# ESP32.net
KiCad netlist of a schematic drawn in Altium Designer
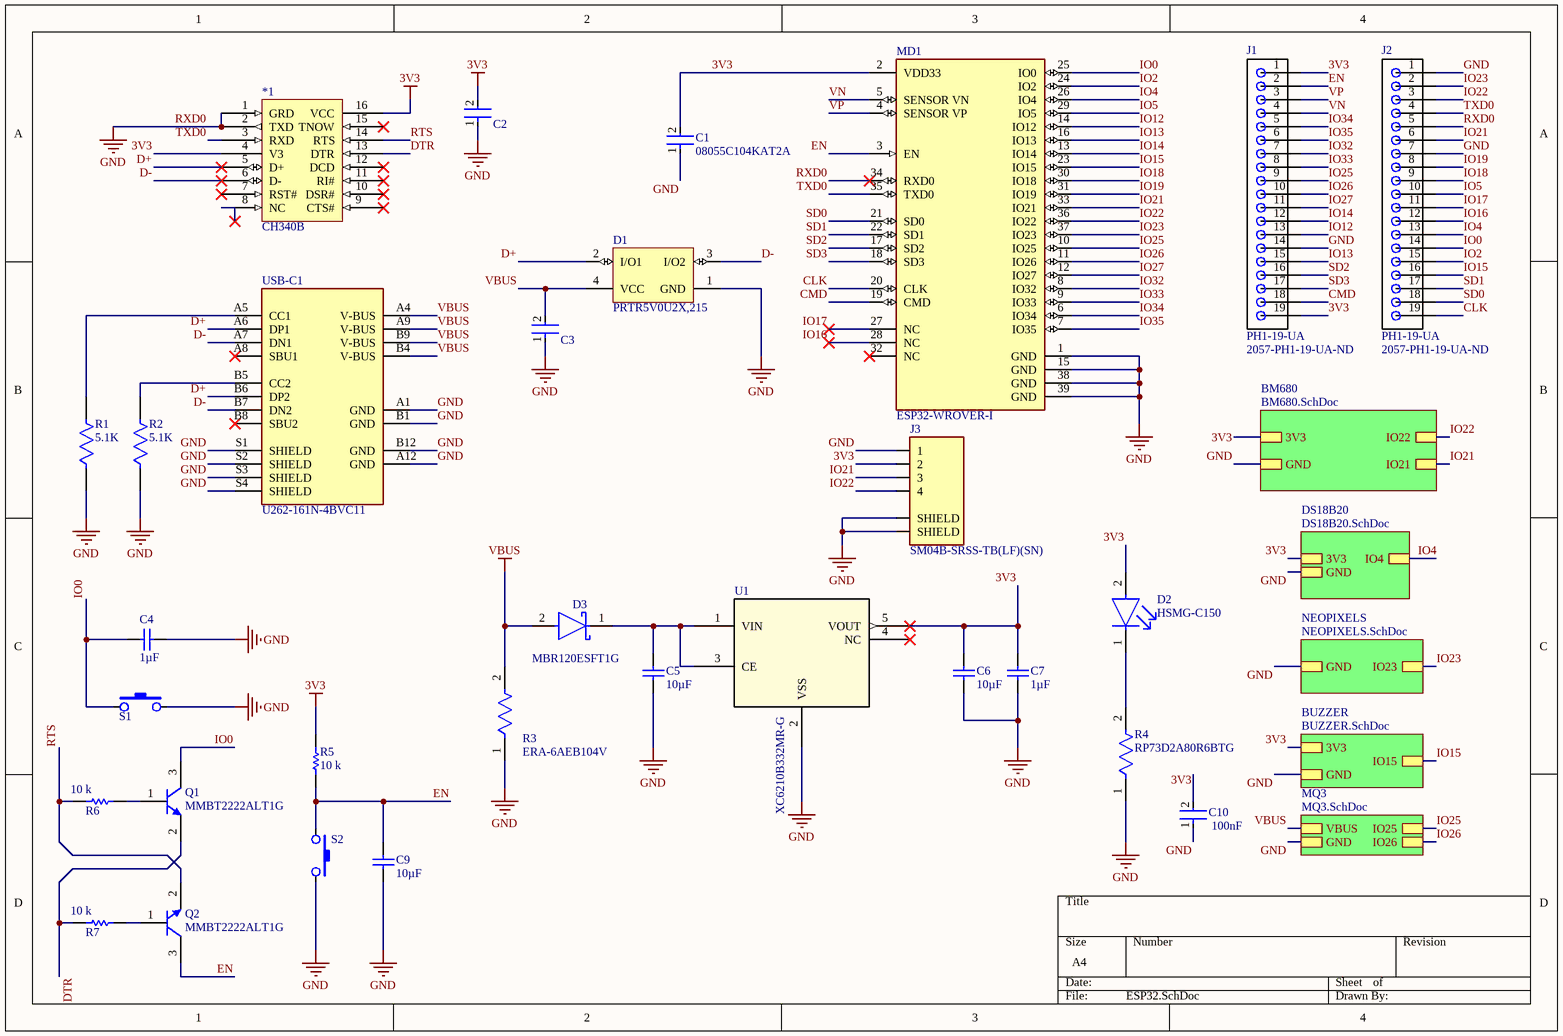
[diagram p0: ESP32.SchDoc]

(export (version "E")
  (design (tool "Eeschema 10.0.6"))
  (components
    (comp (ref "*1")
      (value "CH340B")
      (footprint "CH340B")
      (description "- USB 2.0 Transceiver 2Mbps SOP-16_150mil USB ICs ROHS")
      (libsource (lib "Isidro_Library") (part "CH340B"))
    )
    (comp (ref "C1")
      (value "08055C104KAT2A")
      (footprint "FP-0805-L_2_01_0_2-W_1_25-IPC_C")
      (description "General Purpose Ceramic Capacitor, 0805, 100nF, 10%, X7R, 0.15, 50V")
      (fields (field (name "TOLERANCE") "10%") (field (name "VOLTAGE") "50V"))
      (libsource (lib "Altium Content Vault") (part "02cd4be3c70576c341d710602a673aa"))
    )
    (comp (ref "C2")
      (value "08055C104KAT2A")
      (footprint "FP-0805-L_2_01_0_2-W_1_25-IPC_C")
      (description "General Purpose Ceramic Capacitor, 0805, 100nF, 10%, X7R, 0.15, 50V")
      (fields (field (name "TOLERANCE") "10%") (field (name "VOLTAGE") "50V"))
      (libsource (lib "Altium Content Vault") (part "02cd4be3c70576c341d710602a673aa"))
    )
    (comp (ref "C3")
      (value "08055C104KAT2A")
      (footprint "FP-0805-L_2_01_0_2-W_1_25-IPC_C")
      (description "General Purpose Ceramic Capacitor, 0805, 100nF, 10%, X7R, 0.15, 50V")
      (fields (field (name "TOLERANCE") "10%") (field (name "VOLTAGE") "50V"))
      (libsource (lib "Altium Content Vault") (part "02cd4be3c70576c341d710602a673aa"))
    )
    (comp (ref "C4")
      (value "1µF")
      (footprint "CAPC2013X145X50LL20T25")
      (description "1µF ±10% 16V Ceramic Capacitor X7R 0805 (2012 Metric)")
      (fields (field (name "MANUFACTURER") "Kemet") (field (name "PART NUMBER") "C0805C105K4RAC7800"))
      (libsource (lib "Altium Content Vault") (part "CAP"))
    )
    (comp (ref "C5")
      (value "10µF")
      (footprint "CAPC2013X140X50LL20T25")
      (description "10µF ±10% 16V Ceramic Capacitor X5R 0805 (2012 Metric)")
      (fields (field (name "PART NUMBER") "CL21A106KOQNNNG"))
      (libsource (lib "Altium Content Vault") (part "CAP"))
    )
    (comp (ref "C6")
      (value "10µF")
      (footprint "CAPC2013X140X50LL20T25")
      (description "10µF ±10% 16V Ceramic Capacitor X5R 0805 (2012 Metric)")
      (fields (field (name "PART NUMBER") "CL21A106KOQNNNG"))
      (libsource (lib "Altium Content Vault") (part "CAP"))
    )
    (comp (ref "C7")
      (value "1µF")
      (footprint "CAPC2013X145X50LL20T25")
      (description "1µF ±10% 16V Ceramic Capacitor X7R 0805 (2012 Metric)")
      (fields (field (name "MANUFACTURER") "Kemet") (field (name "PART NUMBER") "C0805C105K4RAC7800"))
      (libsource (lib "Altium Content Vault") (part "CAP"))
    )
    (comp (ref "C9")
      (value "10µF")
      (footprint "CAPC2013X145X50LL20T25")
      (description "1µF ±10% 16V Ceramic Capacitor X7R 0805 (2012 Metric)")
      (fields (field (name "MANUFACTURER") "Kemet") (field (name "PART NUMBER") "C0805C105K4RAC7800"))
      (libsource (lib "Altium Content Vault") (part "CAP"))
    )
    (comp (ref "C10")
      (value "100nF")
      (footprint "FP-0805-L_2_01_0_2-W_1_25-IPC_C")
      (description "General Purpose Ceramic Capacitor, 0805, 100nF, 10%, X7R, 0.15, 50V")
      (fields (field (name "TOLERANCE") "10%") (field (name "VOLTAGE") "50V"))
      (libsource (lib "Altium Content Vault") (part "02cd4be3c70576c341d710602a673aa"))
    )
    (comp (ref "D1")
      (value "PRTR5V0U2X,215")
      (footprint "NXP-SOT143B-4_V")
      (fields (field (name "MANUFACTURER") "NXP Semiconductors"))
      (libsource (lib "Altium Content Vault") (part "NXP-PRTR5V0U2X,215-4"))
    )
    (comp (ref "D2")
      (value "HSMG-C150")
      (footprint "FP-HSMG-C150-MFG")
      (description "LED GREEN DIFFUSED 1206 SMD")
      (fields
        (field (name "MANUFACTURER") "Broadcom")
        (field (name "OCTOPART") "https://octopart.com/hsmg-c150-broadcom-71131304")
      )
      (libsource (lib "Altium Content Vault") (part "8706943c75ba83719d021d2fdc84c58"))
    )
    (comp (ref "D3")
      (value "MBR120ESFT1G")
      (footprint "On_Semiconductor_498_MFG")
      (libsource (lib "Altium Content Vault") (part "MBR120ESFT1G"))
    )
    (comp (ref "J1")
      (value "PH1-19-UA")
      (footprint "PH1-19-UA")
      (description "Connector Header Through Hole 19 position 0.100\" (2.54mm)")
      (fields (field (name "SUPPLIER PART NUMBER 1") "2057-PH1-19-UA-ND"))
      (libsource (lib "Isidro_Library") (part "PH1-19-UA"))
    )
    (comp (ref "J2")
      (value "PH1-19-UA")
      (footprint "PH1-19-UA")
      (description "Connector Header Through Hole 19 position 0.100\" (2.54mm)")
      (fields (field (name "SUPPLIER PART NUMBER 1") "2057-PH1-19-UA-ND"))
      (libsource (lib "Isidro_Library") (part "PH1-19-UA"))
    )
    (comp (ref "J3")
      (value "SM04B-SRSS-TB(LF)(SN)")
      (footprint "JST_SM04B-SRSS-TB(LF)(SN)")
      (description "Connector Header Surface Mount, Right Angle 4 position 0.039 _1.00mm_")
      (fields (field (name "MF") "JST Sales") (field (name "MP") "SM04B-SRSS-TB_LF__SN_"))
      (libsource (lib "Isidro_Library") (part "SM04B-SRSS-TB(LF)(SN)"))
    )
    (comp (ref "MD1")
      (value "ESP32-WROVER-I")
      (footprint "FP-ESP32-WROVER-I-MFG")
      (description "SMD MODULE, ESP32-D0WDQ6, 32MBIT")
      (fields
        (field (name "MANUFACTURER") "Espressif")
        (field (name "OCTOPART") "https://octopart.com/esp32-wrover-i-espressif+systems-89171349")
      )
      (libsource (lib "Altium Content Vault") (part "cbbb37af8bcfe61dfd46ac9418f0340"))
    )
    (comp (ref "Q1")
      (value "MMBT2222ALT1G")
      (footprint "ONSC-SOT-23-3-318-08_V")
      (description "General Purpose Transistor, NPN Silicon, 3-Pin SOT-23, Pb-Free, Tape and Reel")
      (fields (field (name "MANUFACTURER") "On Semiconductor"))
      (libsource (lib "Altium Content Vault") (part "ONSC-NPN-B1E2C3-3"))
    )
    (comp (ref "Q2")
      (value "MMBT2222ALT1G")
      (footprint "ONSC-SOT-23-3-318-08_V")
      (description "General Purpose Transistor, NPN Silicon, 3-Pin SOT-23, Pb-Free, Tape and Reel")
      (fields (field (name "MANUFACTURER") "On Semiconductor"))
      (libsource (lib "Altium Content Vault") (part "ONSC-NPN-B1E2C3-3"))
    )
    (comp (ref "R1")
      (value "5.1K")
      (footprint "FP-CRCW0805-e3-IPC_A")
      (description "RES Thick Film, 5.1kΩ, 1%, 0.125W, 100ppm/°C, 0805")
      (fields (field (name "TOLERANCE") "1%"))
      (libsource (lib "") (part "1029c3af85768c4190bb7ad29bc67b5_1"))
    )
    (comp (ref "R2")
      (value "5.1K")
      (footprint "FP-CRCW0805-e3-MFG")
      (description "RES Thick Film, 5.1kΩ, 1%, 0.125W, 100ppm/°C, 0805")
      (fields (field (name "TOLERANCE") "1%"))
      (libsource (lib "") (part "1029c3af85768c4190bb7ad29bc67b5_1"))
    )
    (comp (ref "R3")
      (value "ERA-6AEB104V")
      (footprint "FP-ERA6A-IPC_B")
      (description "RES 100K OHM 0.1% 1/8W 0805")
      (fields (field (name "TOLERANCE") "0.1%"))
      (libsource (lib "Altium Content Vault") (part "1029c3af85768c4190bb7ad29bc67b5"))
    )
    (comp (ref "R4")
      (value "RP73D2A80R6BTG")
      (footprint "FP-RP732A-IPC_A")
      (description "RESISTOR, 0805 80.6Ω, 0.1% 15ppm/°C")
      (fields
        (field (name "OCTOPART") "https://octopart.com/rp73d2a80r6btg-te+connectivity-42011633")
        (field (name "MANUFACTURER") "TE Connectivity")
      )
      (libsource (lib "Altium Content Vault") (part "1029c3af85768c4190bb7ad29bc67b5"))
    )
    (comp (ref "R5")
      (value "10 k")
      (footprint "RESC2013X60X30LL20T20")
      (fields (field (name "PART NUMBER") "RK73B2ATTD103J") (field (name "MANUFACTURER") "KOA Speer"))
      (libsource (lib "Altium Content Vault") (part "RES"))
    )
    (comp (ref "R6")
      (value "10 k")
      (footprint "RESC2013X60X30LL20T20")
      (fields (field (name "PART NUMBER") "RK73B2ATTD103J") (field (name "MANUFACTURER") "KOA Speer"))
      (libsource (lib "Altium Content Vault") (part "RES"))
    )
    (comp (ref "R7")
      (value "10 k")
      (footprint "RESC2013X60X30LL20T20")
      (fields (field (name "PART NUMBER") "RK73B2ATTD103J") (field (name "MANUFACTURER") "KOA Speer"))
      (libsource (lib "Altium Content Vault") (part "RES"))
    )
    (comp (ref "S1")
      (value "IO0")
      (footprint "SMT_SW_PTS_820")
      (libsource (lib "SnapEDAsch") (part "PTS820J25MSMTRLFS"))
    )
    (comp (ref "S2")
      (value "PTS820J25MSMTRLFS")
      (footprint "SMT_SW_PTS_820")
      (libsource (lib "SnapEDAsch") (part "PTS820J25MSMTRLFS"))
    )
    (comp (ref "U1")
      (value "XC6210B332MR-G")
      (footprint "SOT-25_TOR-M")
      (description "No Description Available")
      (fields (field (name "COPYRIGHT") "Copyright (C) 2022 Ultra Librarian. All rights reserved."))
      (libsource (lib "Isidro_Library") (part "XC6210B332MR-G"))
    )
    (comp (ref "USB-C1")
      (value "U262-161N-4BVC11")
      (footprint "U262-161N-4BVC11")
      (description "USB - Type C Female 16 SMT USB Connectors RoHS")
      (libsource (lib "AQIMon") (part "U262-161N-4BVC11"))
    )
  )
  (nets
    (net (code "1") (name "/CLK") (class "Default")
      (node (ref "J2") (pin "19") (pinfunction "19_19") (pintype "passive"))
      (node (ref "MD1") (pin "20") (pinfunction "CLK_20") (pintype "bidirectional"))
    )
    (net (code "2") (name "/CMD") (class "Default")
      (node (ref "J1") (pin "18") (pinfunction "18_18") (pintype "passive"))
      (node (ref "MD1") (pin "19") (pinfunction "CMD_19") (pintype "bidirectional"))
    )
    (net (code "3") (name "/D+") (class "Default")
      (node (ref "*1") (pin "5") (pinfunction "D+_5") (pintype "bidirectional"))
      (node (ref "D1") (pin "2") (pinfunction "I/O1_2") (pintype "bidirectional"))
      (node (ref "USB-C1") (pin "A6") (pinfunction "DP1_A6") (pintype "power_in"))
      (node (ref "USB-C1") (pin "B6") (pinfunction "DP2_B6") (pintype "power_in"))
    )
    (net (code "4") (name "/D-") (class "Default")
      (node (ref "*1") (pin "6") (pinfunction "D-_6") (pintype "bidirectional"))
      (node (ref "D1") (pin "3") (pinfunction "I/O2_3") (pintype "bidirectional"))
      (node (ref "USB-C1") (pin "A7") (pinfunction "DN1_A7") (pintype "power_in"))
      (node (ref "USB-C1") (pin "B7") (pinfunction "DN2_B7") (pintype "power_in"))
    )
    (net (code "5") (name "/DTR") (class "Default")
      (node (ref "*1") (pin "13") (pinfunction "DTR_13") (pintype "input"))
      (node (ref "Q1") (pin "2") (pinfunction "E_2") (pintype "passive"))
      (node (ref "R7") (pin "2") (pinfunction "2_2") (pintype "passive"))
    )
    (net (code "6") (name "/EN") (class "Default")
      (node (ref "C9") (pin "2") (pinfunction "2_2") (pintype "passive"))
      (node (ref "J1") (pin "2") (pinfunction "2_2") (pintype "passive"))
      (node (ref "MD1") (pin "3") (pinfunction "EN_3") (pintype "input"))
      (node (ref "Q2") (pin "3") (pinfunction "C_3") (pintype "passive"))
      (node (ref "R5") (pin "1") (pinfunction "1_1") (pintype "passive"))
      (node (ref "S2") (pin "1") (pinfunction "1_1") (pintype "passive"))
    )
    (net (code "7") (name "/IO0") (class "Default")
      (node (ref "C4") (pin "2") (pinfunction "2_2") (pintype "passive"))
      (node (ref "J2") (pin "14") (pinfunction "14_14") (pintype "passive"))
      (node (ref "MD1") (pin "25") (pinfunction "IO0_25") (pintype "bidirectional"))
      (node (ref "Q1") (pin "3") (pinfunction "C_3") (pintype "passive"))
      (node (ref "S1") (pin "1") (pinfunction "1_1") (pintype "passive"))
    )
    (net (code "8") (name "/IO2") (class "Default")
      (node (ref "J2") (pin "15") (pinfunction "15_15") (pintype "passive"))
      (node (ref "MD1") (pin "24") (pinfunction "IO2_24") (pintype "bidirectional"))
    )
    (net (code "9") (name "/IO4") (class "Default")
      (node (ref "J2") (pin "13") (pinfunction "13_13") (pintype "passive"))
      (node (ref "MD1") (pin "26") (pinfunction "IO4_26") (pintype "bidirectional"))
    )
    (net (code "10") (name "/IO5") (class "Default")
      (node (ref "J2") (pin "10") (pinfunction "10_10") (pintype "passive"))
      (node (ref "MD1") (pin "29") (pinfunction "IO5_29") (pintype "bidirectional"))
    )
    (net (code "11") (name "/IO12") (class "Default")
      (node (ref "J1") (pin "13") (pinfunction "13_13") (pintype "passive"))
      (node (ref "MD1") (pin "14") (pinfunction "IO12_14") (pintype "bidirectional"))
    )
    (net (code "12") (name "/IO13") (class "Default")
      (node (ref "J1") (pin "15") (pinfunction "15_15") (pintype "passive"))
      (node (ref "MD1") (pin "16") (pinfunction "IO13_16") (pintype "bidirectional"))
    )
    (net (code "13") (name "/IO14") (class "Default")
      (node (ref "J1") (pin "12") (pinfunction "12_12") (pintype "passive"))
      (node (ref "MD1") (pin "13") (pinfunction "IO14_13") (pintype "bidirectional"))
    )
    (net (code "14") (name "/IO15") (class "Default")
      (node (ref "J2") (pin "16") (pinfunction "16_16") (pintype "passive"))
      (node (ref "MD1") (pin "23") (pinfunction "IO15_23") (pintype "bidirectional"))
    )
    (net (code "15") (name "/IO16") (class "Default")
      (node (ref "J2") (pin "12") (pinfunction "12_12") (pintype "passive"))
      (node (ref "MD1") (pin "28") (pinfunction "NC_28") (pintype "passive"))
    )
    (net (code "16") (name "/IO17") (class "Default")
      (node (ref "J2") (pin "11") (pinfunction "11_11") (pintype "passive"))
      (node (ref "MD1") (pin "27") (pinfunction "NC_27") (pintype "passive"))
    )
    (net (code "17") (name "/IO18") (class "Default")
      (node (ref "J2") (pin "9") (pinfunction "9_9") (pintype "passive"))
      (node (ref "MD1") (pin "30") (pinfunction "IO18_30") (pintype "bidirectional"))
    )
    (net (code "18") (name "/IO19") (class "Default")
      (node (ref "J2") (pin "8") (pinfunction "8_8") (pintype "passive"))
      (node (ref "MD1") (pin "31") (pinfunction "IO19_31") (pintype "bidirectional"))
    )
    (net (code "19") (name "/IO21") (class "Default")
      (node (ref "J2") (pin "6") (pinfunction "6_6") (pintype "passive"))
      (node (ref "J3") (pin "3") (pinfunction "3_3") (pintype "passive"))
      (node (ref "MD1") (pin "33") (pinfunction "IO21_33") (pintype "bidirectional"))
    )
    (net (code "20") (name "/IO22") (class "Default")
      (node (ref "J2") (pin "3") (pinfunction "3_3") (pintype "passive"))
      (node (ref "J3") (pin "4") (pinfunction "4_4") (pintype "passive"))
      (node (ref "MD1") (pin "36") (pinfunction "IO22_36") (pintype "bidirectional"))
    )
    (net (code "21") (name "/IO23") (class "Default")
      (node (ref "J2") (pin "2") (pinfunction "2_2") (pintype "passive"))
      (node (ref "MD1") (pin "37") (pinfunction "IO23_37") (pintype "bidirectional"))
    )
    (net (code "22") (name "/IO25") (class "Default")
      (node (ref "J1") (pin "9") (pinfunction "9_9") (pintype "passive"))
      (node (ref "MD1") (pin "10") (pinfunction "IO25_10") (pintype "bidirectional"))
    )
    (net (code "23") (name "/IO26") (class "Default")
      (node (ref "J1") (pin "10") (pinfunction "10_10") (pintype "passive"))
      (node (ref "MD1") (pin "11") (pinfunction "IO26_11") (pintype "bidirectional"))
    )
    (net (code "24") (name "/IO27") (class "Default")
      (node (ref "J1") (pin "11") (pinfunction "11_11") (pintype "passive"))
      (node (ref "MD1") (pin "12") (pinfunction "IO27_12") (pintype "bidirectional"))
    )
    (net (code "25") (name "/IO32") (class "Default")
      (node (ref "J1") (pin "7") (pinfunction "7_7") (pintype "passive"))
      (node (ref "MD1") (pin "8") (pinfunction "IO32_8") (pintype "bidirectional"))
    )
    (net (code "26") (name "/IO33") (class "Default")
      (node (ref "J1") (pin "8") (pinfunction "8_8") (pintype "passive"))
      (node (ref "MD1") (pin "9") (pinfunction "IO33_9") (pintype "bidirectional"))
    )
    (net (code "27") (name "/IO34") (class "Default")
      (node (ref "J1") (pin "5") (pinfunction "5_5") (pintype "passive"))
      (node (ref "MD1") (pin "6") (pinfunction "IO34_6") (pintype "bidirectional"))
    )
    (net (code "28") (name "/IO35") (class "Default")
      (node (ref "J1") (pin "6") (pinfunction "6_6") (pintype "passive"))
      (node (ref "MD1") (pin "7") (pinfunction "IO35_7") (pintype "bidirectional"))
    )
    (net (code "29") (name "/RTS") (class "Default")
      (node (ref "*1") (pin "14") (pinfunction "RTS_14") (pintype "input"))
      (node (ref "Q2") (pin "2") (pinfunction "E_2") (pintype "passive"))
      (node (ref "R6") (pin "2") (pinfunction "2_2") (pintype "passive"))
    )
    (net (code "30") (name "/SD0") (class "Default")
      (node (ref "J2") (pin "18") (pinfunction "18_18") (pintype "passive"))
      (node (ref "MD1") (pin "21") (pinfunction "SD0_21") (pintype "bidirectional"))
    )
    (net (code "31") (name "/SD1") (class "Default")
      (node (ref "J2") (pin "17") (pinfunction "17_17") (pintype "passive"))
      (node (ref "MD1") (pin "22") (pinfunction "SD1_22") (pintype "bidirectional"))
    )
    (net (code "32") (name "/SD2") (class "Default")
      (node (ref "J1") (pin "16") (pinfunction "16_16") (pintype "passive"))
      (node (ref "MD1") (pin "17") (pinfunction "SD2_17") (pintype "bidirectional"))
    )
    (net (code "33") (name "/SD3") (class "Default")
      (node (ref "J1") (pin "17") (pinfunction "17_17") (pintype "passive"))
      (node (ref "MD1") (pin "18") (pinfunction "SD3_18") (pintype "bidirectional"))
    )
    (net (code "34") (name "/TXD0") (class "Default")
      (node (ref "*1") (pin "3") (pinfunction "RXD_3") (pintype "input"))
      (node (ref "J2") (pin "4") (pinfunction "4_4") (pintype "passive"))
      (node (ref "MD1") (pin "35") (pinfunction "TXD0_35") (pintype "bidirectional"))
    )
    (net (code "35") (name "/VN") (class "Default")
      (node (ref "J1") (pin "4") (pinfunction "4_4") (pintype "passive"))
      (node (ref "MD1") (pin "5") (pinfunction "SENSOR_VN_5") (pintype "bidirectional"))
    )
    (net (code "36") (name "/VP") (class "Default")
      (node (ref "J1") (pin "3") (pinfunction "3_3") (pintype "passive"))
      (node (ref "MD1") (pin "4") (pinfunction "SENSOR_VP_4") (pintype "bidirectional"))
    )
    (net (code "37") (name "3V3") (class "Default")
      (node (ref "*1") (pin "16") (pinfunction "VCC_16") (pintype "power_in"))
      (node (ref "*1") (pin "4") (pinfunction "V3_4") (pintype "power_in"))
      (node (ref "C1") (pin "2") (pinfunction "2_2") (pintype "passive"))
      (node (ref "C10") (pin "2") (pinfunction "2_2") (pintype "passive"))
      (node (ref "C2") (pin "2") (pinfunction "2_2") (pintype "passive"))
      (node (ref "C6") (pin "2") (pinfunction "2_2") (pintype "passive"))
      (node (ref "C7") (pin "2") (pinfunction "2_2") (pintype "passive"))
      (node (ref "D2") (pin "2") (pinfunction "A_2") (pintype "passive"))
      (node (ref "J1") (pin "1") (pinfunction "1_1") (pintype "passive"))
      (node (ref "J1") (pin "19") (pinfunction "19_19") (pintype "passive"))
      (node (ref "J3") (pin "2") (pinfunction "2_2") (pintype "passive"))
      (node (ref "MD1") (pin "2") (pinfunction "VDD33_2") (pintype "power_in"))
      (node (ref "R5") (pin "2") (pinfunction "2_2") (pintype "passive"))
      (node (ref "U1") (pin "5") (pinfunction "VOUT_5") (pintype "output"))
    )
    (net (code "38") (name "GND") (class "Default")
      (node (ref "*1") (pin "1") (pinfunction "GRD_1") (pintype "input"))
      (node (ref "*1") (pin "2") (pinfunction "TXD_2") (pintype "output"))
      (node (ref "C1") (pin "1") (pinfunction "1_1") (pintype "passive"))
      (node (ref "C10") (pin "1") (pinfunction "1_1") (pintype "passive"))
      (node (ref "C2") (pin "1") (pinfunction "1_1") (pintype "passive"))
      (node (ref "C3") (pin "1") (pinfunction "1_1") (pintype "passive"))
      (node (ref "C4") (pin "1") (pinfunction "1_1") (pintype "passive"))
      (node (ref "C5") (pin "1") (pinfunction "1_1") (pintype "passive"))
      (node (ref "C6") (pin "1") (pinfunction "1_1") (pintype "passive"))
      (node (ref "C7") (pin "1") (pinfunction "1_1") (pintype "passive"))
      (node (ref "C9") (pin "1") (pinfunction "1_1") (pintype "passive"))
      (node (ref "D1") (pin "1") (pinfunction "GND_1") (pintype "power_in"))
      (node (ref "J1") (pin "14") (pinfunction "14_14") (pintype "passive"))
      (node (ref "J2") (pin "1") (pinfunction "1_1") (pintype "passive"))
      (node (ref "J2") (pin "5") (pinfunction "5_5") (pintype "passive"))
      (node (ref "J2") (pin "7") (pinfunction "7_7") (pintype "passive"))
      (node (ref "J3") (pin "1") (pinfunction "1_1") (pintype "passive"))
      (node (ref "J3") (pin "S1") (pinfunction "SHIELD_S1") (pintype "passive"))
      (node (ref "J3") (pin "S2") (pinfunction "SHIELD_S2") (pintype "passive"))
      (node (ref "MD1") (pin "1") (pinfunction "GND_1") (pintype "power_in"))
      (node (ref "MD1") (pin "15") (pinfunction "GND_15") (pintype "power_in"))
      (node (ref "MD1") (pin "34") (pinfunction "RXD0_34") (pintype "bidirectional"))
      (node (ref "MD1") (pin "38") (pinfunction "GND_38") (pintype "power_in"))
      (node (ref "MD1") (pin "39") (pinfunction "GND_39") (pintype "power_in"))
      (node (ref "R1") (pin "1") (pinfunction "1_1") (pintype "passive"))
      (node (ref "R2") (pin "1") (pinfunction "1_1") (pintype "passive"))
      (node (ref "R3") (pin "1") (pinfunction "1_1") (pintype "passive"))
      (node (ref "R4") (pin "1") (pinfunction "1_1") (pintype "passive"))
      (node (ref "S1") (pin "2") (pinfunction "2_2") (pintype "passive"))
      (node (ref "S2") (pin "2") (pinfunction "2_2") (pintype "passive"))
      (node (ref "U1") (pin "2") (pinfunction "VSS_2") (pintype "passive"))
      (node (ref "USB-C1") (pin "A1") (pinfunction "GND_A1") (pintype "power_in"))
      (node (ref "USB-C1") (pin "A12") (pinfunction "GND_A12") (pintype "power_in"))
      (node (ref "USB-C1") (pin "B1") (pinfunction "GND_B1") (pintype "power_in"))
      (node (ref "USB-C1") (pin "B12") (pinfunction "GND_B12") (pintype "power_in"))
      (node (ref "USB-C1") (pin "S1") (pinfunction "SHIELD_S1") (pintype "passive"))
      (node (ref "USB-C1") (pin "S2") (pinfunction "SHIELD_S2") (pintype "passive"))
      (node (ref "USB-C1") (pin "S3") (pinfunction "SHIELD_S3") (pintype "passive"))
      (node (ref "USB-C1") (pin "S4") (pinfunction "SHIELD_S4") (pintype "passive"))
    )
    (net (code "39") (name "Net-(D2-C)") (class "Default")
      (node (ref "D2") (pin "1") (pinfunction "C_1") (pintype "passive"))
      (node (ref "R4") (pin "2") (pinfunction "2_2") (pintype "passive"))
    )
    (net (code "40") (name "Net-(D3-C)") (class "Default")
      (node (ref "C5") (pin "2") (pinfunction "2_2") (pintype "passive"))
      (node (ref "D3") (pin "1") (pinfunction "C_1") (pintype "passive"))
      (node (ref "U1") (pin "1") (pinfunction "VIN_1") (pintype "power_in"))
      (node (ref "U1") (pin "3") (pinfunction "CE_3") (pintype "passive"))
    )
    (net (code "41") (name "Net-(Q1-B)") (class "Default")
      (node (ref "Q1") (pin "1") (pinfunction "B_1") (pintype "passive"))
      (node (ref "R6") (pin "1") (pinfunction "1_1") (pintype "passive"))
    )
    (net (code "42") (name "Net-(Q2-B)") (class "Default")
      (node (ref "Q2") (pin "1") (pinfunction "B_1") (pintype "passive"))
      (node (ref "R7") (pin "1") (pinfunction "1_1") (pintype "passive"))
    )
    (net (code "43") (name "Net-(USB-C1-CC1)") (class "Default")
      (node (ref "R1") (pin "2") (pinfunction "2_2") (pintype "passive"))
      (node (ref "USB-C1") (pin "A5") (pinfunction "CC1_A5") (pintype "power_in"))
    )
    (net (code "44") (name "Net-(USB-C1-CC2)") (class "Default")
      (node (ref "R2") (pin "2") (pinfunction "2_2") (pintype "passive"))
      (node (ref "USB-C1") (pin "B5") (pinfunction "CC2_B5") (pintype "power_in"))
    )
    (net (code "45") (name "VBUS") (class "Default")
      (node (ref "C3") (pin "2") (pinfunction "2_2") (pintype "passive"))
      (node (ref "D1") (pin "4") (pinfunction "VCC_4") (pintype "power_in"))
      (node (ref "D3") (pin "2") (pinfunction "A_2") (pintype "passive"))
      (node (ref "R3") (pin "2") (pinfunction "2_2") (pintype "passive"))
      (node (ref "USB-C1") (pin "A4") (pinfunction "V-BUS_A4") (pintype "power_in"))
      (node (ref "USB-C1") (pin "A9") (pinfunction "V-BUS_A9") (pintype "power_in"))
      (node (ref "USB-C1") (pin "B4") (pinfunction "V-BUS_B4") (pintype "power_in"))
      (node (ref "USB-C1") (pin "B9") (pinfunction "V-BUS_B9") (pintype "power_in"))
    )
    (net (code "46") (name "unconnected-(*1-CTS#-Pad9)") (class "Default")
      (node (ref "*1") (pin "9") (pinfunction "CTS#_9") (pintype "input+no_connect"))
    )
    (net (code "47") (name "unconnected-(*1-DCD-Pad12)") (class "Default")
      (node (ref "*1") (pin "12") (pinfunction "DCD_12") (pintype "input+no_connect"))
    )
    (net (code "48") (name "unconnected-(*1-DSR#-Pad10)") (class "Default")
      (node (ref "*1") (pin "10") (pinfunction "DSR#_10") (pintype "input+no_connect"))
    )
    (net (code "49") (name "unconnected-(*1-NC-Pad8)") (class "Default")
      (node (ref "*1") (pin "8") (pinfunction "NC_8") (pintype "input+no_connect"))
    )
    (net (code "50") (name "unconnected-(*1-RI#-Pad11)") (class "Default")
      (node (ref "*1") (pin "11") (pinfunction "RI#_11") (pintype "input+no_connect"))
    )
    (net (code "51") (name "unconnected-(*1-RST#-Pad7)") (class "Default")
      (node (ref "*1") (pin "7") (pinfunction "RST#_7") (pintype "input+no_connect"))
    )
    (net (code "52") (name "unconnected-(*1-TNOW-Pad15)") (class "Default")
      (node (ref "*1") (pin "15") (pinfunction "TNOW_15") (pintype "input+no_connect"))
    )
    (net (code "53") (name "unconnected-(MD1-NC-Pad32)") (class "Default")
      (node (ref "MD1") (pin "32") (pinfunction "NC_32") (pintype "passive+no_connect"))
    )
    (net (code "54") (name "unconnected-(U1-NC-Pad4)") (class "Default")
      (node (ref "U1") (pin "4") (pinfunction "NC_4") (pintype "passive+no_connect"))
    )
    (net (code "55") (name "unconnected-(USB-C1-SBU1-PadA8)") (class "Default")
      (node (ref "USB-C1") (pin "A8") (pinfunction "SBU1_A8") (pintype "power_in+no_connect"))
    )
    (net (code "56") (name "unconnected-(USB-C1-SBU2-PadB8)") (class "Default")
      (node (ref "USB-C1") (pin "B8") (pinfunction "SBU2_B8") (pintype "power_in+no_connect"))
    )
  )
)
